# hexciliaSMD_1.net
KiCad netlist of a schematic drawn in EAGLE
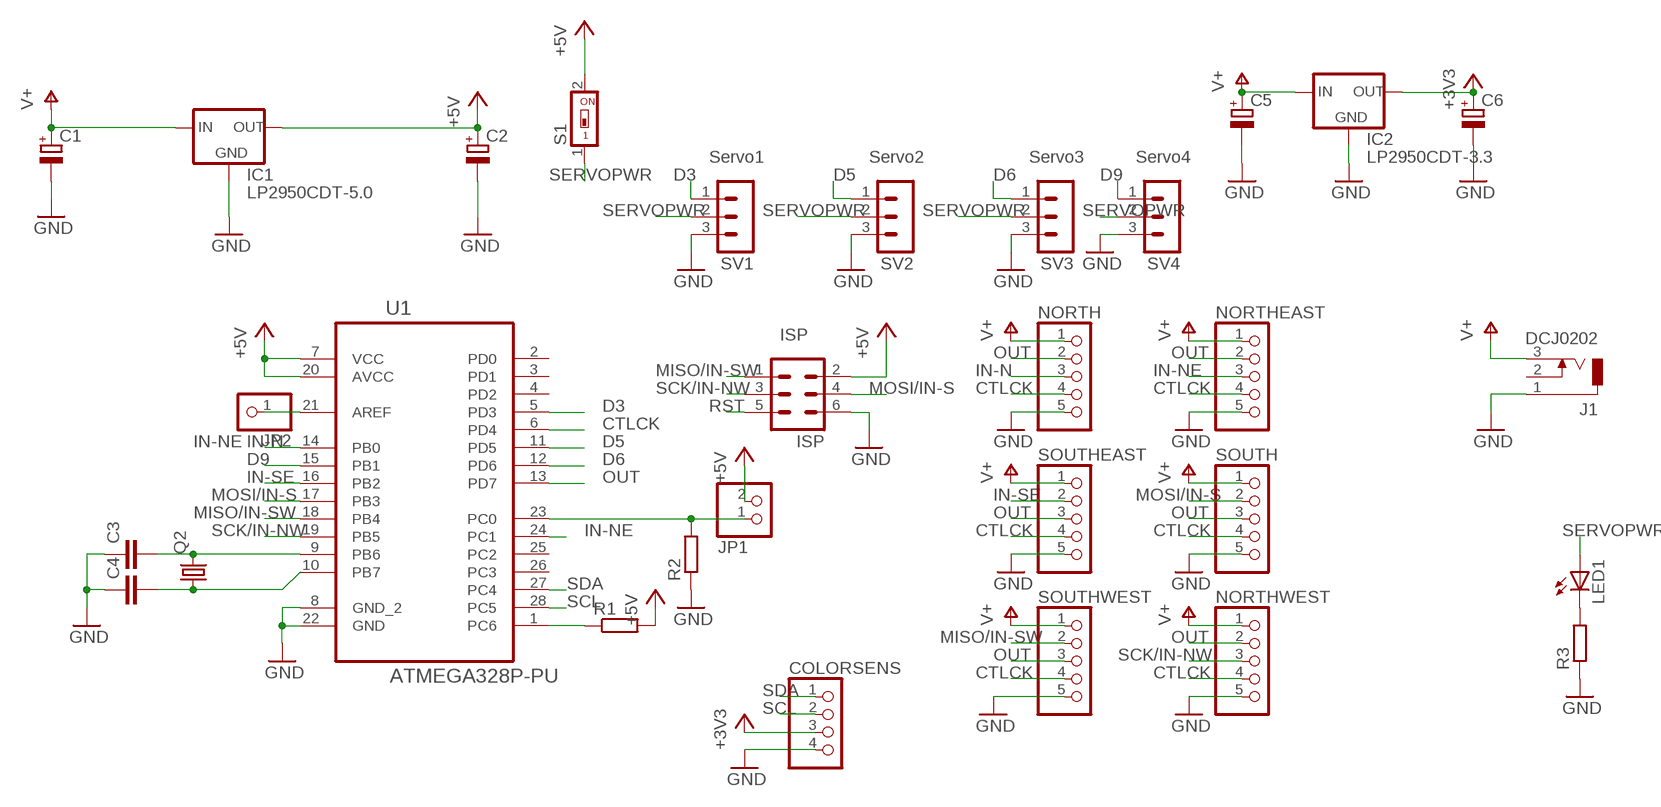
[diagram p0: schematic, sheet 1]

(export (version "E")
  (design (tool "Eeschema 10.0.6"))
  (components
    (comp (ref "C1")
      (value "CPOL-EU153CLV-0605")
      (footprint "eagle-import:153CLV-0605")
      (libsource (lib "eagle-import") (part "CPOL-EU153CLV-0605"))
    )
    (comp (ref "C2")
      (value "CPOL-EU153CLV-0605")
      (footprint "eagle-import:153CLV-0605")
      (libsource (lib "eagle-import") (part "CPOL-EU153CLV-0605"))
    )
    (comp (ref "C3")
      (value "C-EUC1210")
      (footprint "eagle-import:C1210")
      (libsource (lib "eagle-import") (part "C-EUC1210"))
    )
    (comp (ref "C4")
      (value "C-EUC1210")
      (footprint "eagle-import:C1210")
      (libsource (lib "eagle-import") (part "C-EUC1210"))
    )
    (comp (ref "C5")
      (value "CPOL-EU153CLV-0605")
      (footprint "eagle-import:153CLV-0605")
      (libsource (lib "eagle-import") (part "CPOL-EU153CLV-0605"))
    )
    (comp (ref "C6")
      (value "CPOL-EU153CLV-0605")
      (footprint "eagle-import:153CLV-0605")
      (libsource (lib "eagle-import") (part "CPOL-EU153CLV-0605"))
    )
    (comp (ref "COLORSENS")
      (value "PINHD-1X4")
      (footprint "eagle-import:1X04")
      (libsource (lib "eagle-import") (part "PINHD-1X4"))
    )
    (comp (ref "IC1")
      (value "LP2950CDT-5.0")
      (footprint "eagle-import:DPACK")
      (libsource (lib "eagle-import") (part "LP2950?CDT-5.0"))
    )
    (comp (ref "IC2")
      (value "LP2950CDT-3.3")
      (footprint "eagle-import:DPACK")
      (libsource (lib "eagle-import") (part "LP2950?CDT-3.3"))
    )
    (comp (ref "ISP")
      (value "MA03-2")
      (footprint "eagle-import:MA03-2")
      (libsource (lib "eagle-import") (part "MA03-2"))
    )
    (comp (ref "J1")
      (value "DCJ0202")
      (footprint "eagle-import:DCJ0202")
      (libsource (lib "eagle-import") (part "DCJ0202"))
    )
    (comp (ref "JP1")
      (value "PINHD-1X2")
      (footprint "eagle-import:1X02")
      (libsource (lib "eagle-import") (part "PINHD-1X2"))
    )
    (comp (ref "JP2")
      (value "PINHD-1X1")
      (footprint "eagle-import:1X01")
      (libsource (lib "eagle-import") (part "PINHD-1X1"))
    )
    (comp (ref "LED1")
      (value "LEDCHIP-LED0805")
      (footprint "eagle-import:CHIP-LED0805")
      (libsource (lib "eagle-import") (part "LEDCHIP-LED0805"))
    )
    (comp (ref "NORTH")
      (value "PINHD-1X5")
      (footprint "eagle-import:1X05")
      (libsource (lib "eagle-import") (part "PINHD-1X5"))
    )
    (comp (ref "NORTHEAST")
      (value "PINHD-1X5")
      (footprint "eagle-import:1X05")
      (libsource (lib "eagle-import") (part "PINHD-1X5"))
    )
    (comp (ref "NORTHWEST")
      (value "PINHD-1X5")
      (footprint "eagle-import:1X05")
      (libsource (lib "eagle-import") (part "PINHD-1X5"))
    )
    (comp (ref "Q2")
      (value "CRYSTALHC49UP")
      (footprint "eagle-import:HC49UP")
      (libsource (lib "eagle-import") (part "CRYSTALHC49UP"))
    )
    (comp (ref "R1")
      (value "R-EU_M1206")
      (footprint "eagle-import:M1206")
      (libsource (lib "eagle-import") (part "R-EU_M1206"))
    )
    (comp (ref "R2")
      (value "R-EU_M1206")
      (footprint "eagle-import:M1206")
      (libsource (lib "eagle-import") (part "R-EU_M1206"))
    )
    (comp (ref "R3")
      (value "R-EU_M1206")
      (footprint "eagle-import:M1206")
      (libsource (lib "eagle-import") (part "R-EU_M1206"))
    )
    (comp (ref "S1")
      (value "SWS001")
      (footprint "eagle-import:SMS-001")
      (libsource (lib "eagle-import") (part "SWS001"))
    )
    (comp (ref "SOUTH")
      (value "PINHD-1X5")
      (footprint "eagle-import:1X05")
      (libsource (lib "eagle-import") (part "PINHD-1X5"))
    )
    (comp (ref "SOUTHEAST")
      (value "PINHD-1X5")
      (footprint "eagle-import:1X05")
      (libsource (lib "eagle-import") (part "PINHD-1X5"))
    )
    (comp (ref "SOUTHWEST")
      (value "PINHD-1X5")
      (footprint "eagle-import:1X05")
      (libsource (lib "eagle-import") (part "PINHD-1X5"))
    )
    (comp (ref "SV1")
      (value "MA03-1")
      (footprint "eagle-import:MA03-1")
      (libsource (lib "eagle-import") (part "MA03-1"))
    )
    (comp (ref "SV2")
      (value "MA03-1")
      (footprint "eagle-import:MA03-1")
      (libsource (lib "eagle-import") (part "MA03-1"))
    )
    (comp (ref "SV3")
      (value "MA03-1")
      (footprint "eagle-import:MA03-1")
      (libsource (lib "eagle-import") (part "MA03-1"))
    )
    (comp (ref "SV4")
      (value "MA03-1")
      (footprint "eagle-import:MA03-1")
      (libsource (lib "eagle-import") (part "MA03-1"))
    )
    (comp (ref "U1")
      (value "ATMEGA328P-PU")
      (footprint "eagle-import:DIP254P762X457-28")
      (libsource (lib "eagle-import") (part "ATMEGA328P-PU"))
    )
  )
  (nets
    (net (code "1") (name "+3V3") (class "Default")
      (node (ref "C6") (pin "+") (pinfunction "+_+") (pintype "passive"))
      (node (ref "COLORSENS") (pin "3") (pinfunction "3_3") (pintype "passive"))
      (node (ref "IC2") (pin "3") (pinfunction "OUT_3") (pintype "passive"))
    )
    (net (code "2") (name "+5V") (class "Default")
      (node (ref "C2") (pin "+") (pinfunction "+_+") (pintype "passive"))
      (node (ref "IC1") (pin "3") (pinfunction "OUT_3") (pintype "passive"))
      (node (ref "ISP") (pin "2") (pinfunction "2_2") (pintype "passive"))
      (node (ref "JP1") (pin "2") (pinfunction "2_2") (pintype "passive"))
      (node (ref "R1") (pin "2") (pinfunction "2_2") (pintype "passive"))
      (node (ref "S1") (pin "2") (pinfunction "2_2") (pintype "passive"))
      (node (ref "U1") (pin "20") (pinfunction "AVCC_20") (pintype "power_in"))
      (node (ref "U1") (pin "7") (pinfunction "VCC_7") (pintype "power_in"))
    )
    (net (code "3") (name "/CONTROLCK") (class "Default")
      (node (ref "NORTH") (pin "4") (pinfunction "4_4") (pintype "passive"))
      (node (ref "NORTHEAST") (pin "4") (pinfunction "4_4") (pintype "passive"))
      (node (ref "NORTHWEST") (pin "4") (pinfunction "4_4") (pintype "passive"))
      (node (ref "SOUTH") (pin "4") (pinfunction "4_4") (pintype "passive"))
      (node (ref "SOUTHEAST") (pin "4") (pinfunction "4_4") (pintype "passive"))
      (node (ref "SOUTHWEST") (pin "4") (pinfunction "4_4") (pintype "passive"))
      (node (ref "U1") (pin "6") (pinfunction "PD4_6") (pintype "bidirectional"))
    )
    (net (code "4") (name "/D3") (class "Default")
      (node (ref "SV1") (pin "1") (pinfunction "1_1") (pintype "passive"))
      (node (ref "U1") (pin "5") (pinfunction "PD3_5") (pintype "bidirectional"))
    )
    (net (code "5") (name "/D5") (class "Default")
      (node (ref "SV2") (pin "1") (pinfunction "1_1") (pintype "passive"))
      (node (ref "U1") (pin "11") (pinfunction "PD5_11") (pintype "bidirectional"))
    )
    (net (code "6") (name "/D6") (class "Default")
      (node (ref "SV3") (pin "1") (pinfunction "1_1") (pintype "passive"))
      (node (ref "U1") (pin "12") (pinfunction "PD6_12") (pintype "bidirectional"))
    )
    (net (code "7") (name "/D9") (class "Default")
      (node (ref "SV4") (pin "1") (pinfunction "1_1") (pintype "passive"))
      (node (ref "U1") (pin "15") (pinfunction "PB1_15") (pintype "bidirectional"))
    )
    (net (code "8") (name "/IN-N") (class "Default")
      (node (ref "NORTH") (pin "3") (pinfunction "3_3") (pintype "passive"))
      (node (ref "U1") (pin "14") (pinfunction "PB0_14") (pintype "bidirectional"))
    )
    (net (code "9") (name "/IN-NE") (class "Default")
      (node (ref "NORTHEAST") (pin "3") (pinfunction "3_3") (pintype "passive"))
      (node (ref "U1") (pin "24") (pinfunction "PC1_24") (pintype "bidirectional"))
    )
    (net (code "10") (name "/IN-SE") (class "Default")
      (node (ref "SOUTHEAST") (pin "2") (pinfunction "2_2") (pintype "passive"))
      (node (ref "U1") (pin "16") (pinfunction "PB2_16") (pintype "bidirectional"))
    )
    (net (code "11") (name "/MISO{slash}IN-SW") (class "Default")
      (node (ref "ISP") (pin "1") (pinfunction "1_1") (pintype "passive"))
      (node (ref "SOUTHWEST") (pin "2") (pinfunction "2_2") (pintype "passive"))
      (node (ref "U1") (pin "18") (pinfunction "PB4_18") (pintype "bidirectional"))
    )
    (net (code "12") (name "/MOSI{slash}IN-S") (class "Default")
      (node (ref "ISP") (pin "4") (pinfunction "4_4") (pintype "passive"))
      (node (ref "SOUTH") (pin "2") (pinfunction "2_2") (pintype "passive"))
      (node (ref "U1") (pin "17") (pinfunction "PB3_17") (pintype "bidirectional"))
    )
    (net (code "13") (name "/OUT") (class "Default")
      (node (ref "NORTH") (pin "2") (pinfunction "2_2") (pintype "passive"))
      (node (ref "NORTHEAST") (pin "2") (pinfunction "2_2") (pintype "passive"))
      (node (ref "NORTHWEST") (pin "2") (pinfunction "2_2") (pintype "passive"))
      (node (ref "SOUTH") (pin "3") (pinfunction "3_3") (pintype "passive"))
      (node (ref "SOUTHEAST") (pin "3") (pinfunction "3_3") (pintype "passive"))
      (node (ref "SOUTHWEST") (pin "3") (pinfunction "3_3") (pintype "passive"))
      (node (ref "U1") (pin "13") (pinfunction "PD7_13") (pintype "bidirectional"))
    )
    (net (code "14") (name "/RST") (class "Default")
      (node (ref "ISP") (pin "5") (pinfunction "5_5") (pintype "passive"))
      (node (ref "R1") (pin "1") (pinfunction "1_1") (pintype "passive"))
      (node (ref "U1") (pin "1") (pinfunction "PC6_1") (pintype "bidirectional"))
    )
    (net (code "15") (name "/SCK{slash}IN-NW") (class "Default")
      (node (ref "ISP") (pin "3") (pinfunction "3_3") (pintype "passive"))
      (node (ref "NORTHWEST") (pin "3") (pinfunction "3_3") (pintype "passive"))
      (node (ref "U1") (pin "19") (pinfunction "PB5_19") (pintype "bidirectional"))
    )
    (net (code "16") (name "/SCL") (class "Default")
      (node (ref "COLORSENS") (pin "2") (pinfunction "2_2") (pintype "passive"))
      (node (ref "U1") (pin "28") (pinfunction "PC5_28") (pintype "bidirectional"))
    )
    (net (code "17") (name "/SDA") (class "Default")
      (node (ref "COLORSENS") (pin "1") (pinfunction "1_1") (pintype "passive"))
      (node (ref "U1") (pin "27") (pinfunction "PC4_27") (pintype "bidirectional"))
    )
    (net (code "18") (name "/SWPWR") (class "Default")
      (node (ref "LED1") (pin "A") (pinfunction "A_A") (pintype "passive"))
      (node (ref "S1") (pin "1") (pinfunction "1_1") (pintype "passive"))
      (node (ref "SV1") (pin "2") (pinfunction "2_2") (pintype "passive"))
      (node (ref "SV2") (pin "2") (pinfunction "2_2") (pintype "passive"))
      (node (ref "SV3") (pin "2") (pinfunction "2_2") (pintype "passive"))
      (node (ref "SV4") (pin "2") (pinfunction "2_2") (pintype "passive"))
    )
    (net (code "19") (name "GND") (class "Default")
      (node (ref "C1") (pin "-") (pinfunction "-_-") (pintype "passive"))
      (node (ref "C2") (pin "-") (pinfunction "-_-") (pintype "passive"))
      (node (ref "C3") (pin "1") (pinfunction "1_1") (pintype "passive"))
      (node (ref "C4") (pin "1") (pinfunction "1_1") (pintype "passive"))
      (node (ref "C5") (pin "-") (pinfunction "-_-") (pintype "passive"))
      (node (ref "C6") (pin "-") (pinfunction "-_-") (pintype "passive"))
      (node (ref "COLORSENS") (pin "4") (pinfunction "4_4") (pintype "passive"))
      (node (ref "IC1") (pin "4") (pinfunction "GND_4") (pintype "input"))
      (node (ref "IC2") (pin "4") (pinfunction "GND_4") (pintype "input"))
      (node (ref "ISP") (pin "6") (pinfunction "6_6") (pintype "passive"))
      (node (ref "J1") (pin "1") (pinfunction "1_1") (pintype "passive"))
      (node (ref "NORTH") (pin "5") (pinfunction "5_5") (pintype "passive"))
      (node (ref "NORTHEAST") (pin "5") (pinfunction "5_5") (pintype "passive"))
      (node (ref "NORTHWEST") (pin "5") (pinfunction "5_5") (pintype "passive"))
      (node (ref "R2") (pin "1") (pinfunction "1_1") (pintype "passive"))
      (node (ref "R3") (pin "1") (pinfunction "1_1") (pintype "passive"))
      (node (ref "SOUTH") (pin "5") (pinfunction "5_5") (pintype "passive"))
      (node (ref "SOUTHEAST") (pin "5") (pinfunction "5_5") (pintype "passive"))
      (node (ref "SOUTHWEST") (pin "5") (pinfunction "5_5") (pintype "passive"))
      (node (ref "SV1") (pin "3") (pinfunction "3_3") (pintype "passive"))
      (node (ref "SV2") (pin "3") (pinfunction "3_3") (pintype "passive"))
      (node (ref "SV3") (pin "3") (pinfunction "3_3") (pintype "passive"))
      (node (ref "SV4") (pin "3") (pinfunction "3_3") (pintype "passive"))
      (node (ref "U1") (pin "22") (pinfunction "GND_22") (pintype "passive"))
      (node (ref "U1") (pin "8") (pinfunction "GND_2_8") (pintype "passive"))
    )
    (net (code "20") (name "Net-(LED1-PadC)") (class "Default")
      (node (ref "LED1") (pin "C") (pinfunction "C_C") (pintype "passive"))
      (node (ref "R3") (pin "2") (pinfunction "2_2") (pintype "passive"))
    )
    (net (code "21") (name "Net-(U1-AREF)") (class "Default")
      (node (ref "JP2") (pin "1") (pinfunction "1_1") (pintype "passive"))
      (node (ref "U1") (pin "21") (pinfunction "AREF_21") (pintype "input"))
    )
    (net (code "22") (name "Net-(U1-PB6)") (class "Default")
      (node (ref "C3") (pin "2") (pinfunction "2_2") (pintype "passive"))
      (node (ref "Q2") (pin "2") (pinfunction "2_2") (pintype "passive"))
      (node (ref "U1") (pin "9") (pinfunction "PB6_9") (pintype "bidirectional"))
    )
    (net (code "23") (name "Net-(U1-PB7)") (class "Default")
      (node (ref "C4") (pin "2") (pinfunction "2_2") (pintype "passive"))
      (node (ref "Q2") (pin "1") (pinfunction "1_1") (pintype "passive"))
      (node (ref "U1") (pin "10") (pinfunction "PB7_10") (pintype "bidirectional"))
    )
    (net (code "24") (name "Net-(U1-PC0)") (class "Default")
      (node (ref "JP1") (pin "1") (pinfunction "1_1") (pintype "passive"))
      (node (ref "R2") (pin "2") (pinfunction "2_2") (pintype "passive"))
      (node (ref "U1") (pin "23") (pinfunction "PC0_23") (pintype "bidirectional"))
    )
    (net (code "25") (name "V+") (class "Default")
      (node (ref "C1") (pin "+") (pinfunction "+_+") (pintype "passive"))
      (node (ref "C5") (pin "+") (pinfunction "+_+") (pintype "passive"))
      (node (ref "IC1") (pin "1") (pinfunction "IN_1") (pintype "input"))
      (node (ref "IC2") (pin "1") (pinfunction "IN_1") (pintype "input"))
      (node (ref "J1") (pin "3") (pinfunction "3_3") (pintype "passive"))
      (node (ref "NORTH") (pin "1") (pinfunction "1_1") (pintype "passive"))
      (node (ref "NORTHEAST") (pin "1") (pinfunction "1_1") (pintype "passive"))
      (node (ref "NORTHWEST") (pin "1") (pinfunction "1_1") (pintype "passive"))
      (node (ref "SOUTH") (pin "1") (pinfunction "1_1") (pintype "passive"))
      (node (ref "SOUTHEAST") (pin "1") (pinfunction "1_1") (pintype "passive"))
      (node (ref "SOUTHWEST") (pin "1") (pinfunction "1_1") (pintype "passive"))
    )
    (net (code "26") (name "unconnected-(J1-Pad2)") (class "Default")
      (node (ref "J1") (pin "2") (pinfunction "2_2") (pintype "passive"))
    )
    (net (code "27") (name "unconnected-(U1-PC2-Pad25)") (class "Default")
      (node (ref "U1") (pin "25") (pinfunction "PC2_25") (pintype "bidirectional"))
    )
    (net (code "28") (name "unconnected-(U1-PC3-Pad26)") (class "Default")
      (node (ref "U1") (pin "26") (pinfunction "PC3_26") (pintype "bidirectional"))
    )
    (net (code "29") (name "unconnected-(U1-PD0-Pad2)") (class "Default")
      (node (ref "U1") (pin "2") (pinfunction "PD0_2") (pintype "bidirectional"))
    )
    (net (code "30") (name "unconnected-(U1-PD1-Pad3)") (class "Default")
      (node (ref "U1") (pin "3") (pinfunction "PD1_3") (pintype "bidirectional"))
    )
    (net (code "31") (name "unconnected-(U1-PD2-Pad4)") (class "Default")
      (node (ref "U1") (pin "4") (pinfunction "PD2_4") (pintype "bidirectional"))
    )
  )
)
